# sensor_module.net
KiCad netlist of a schematic drawn in EAGLE
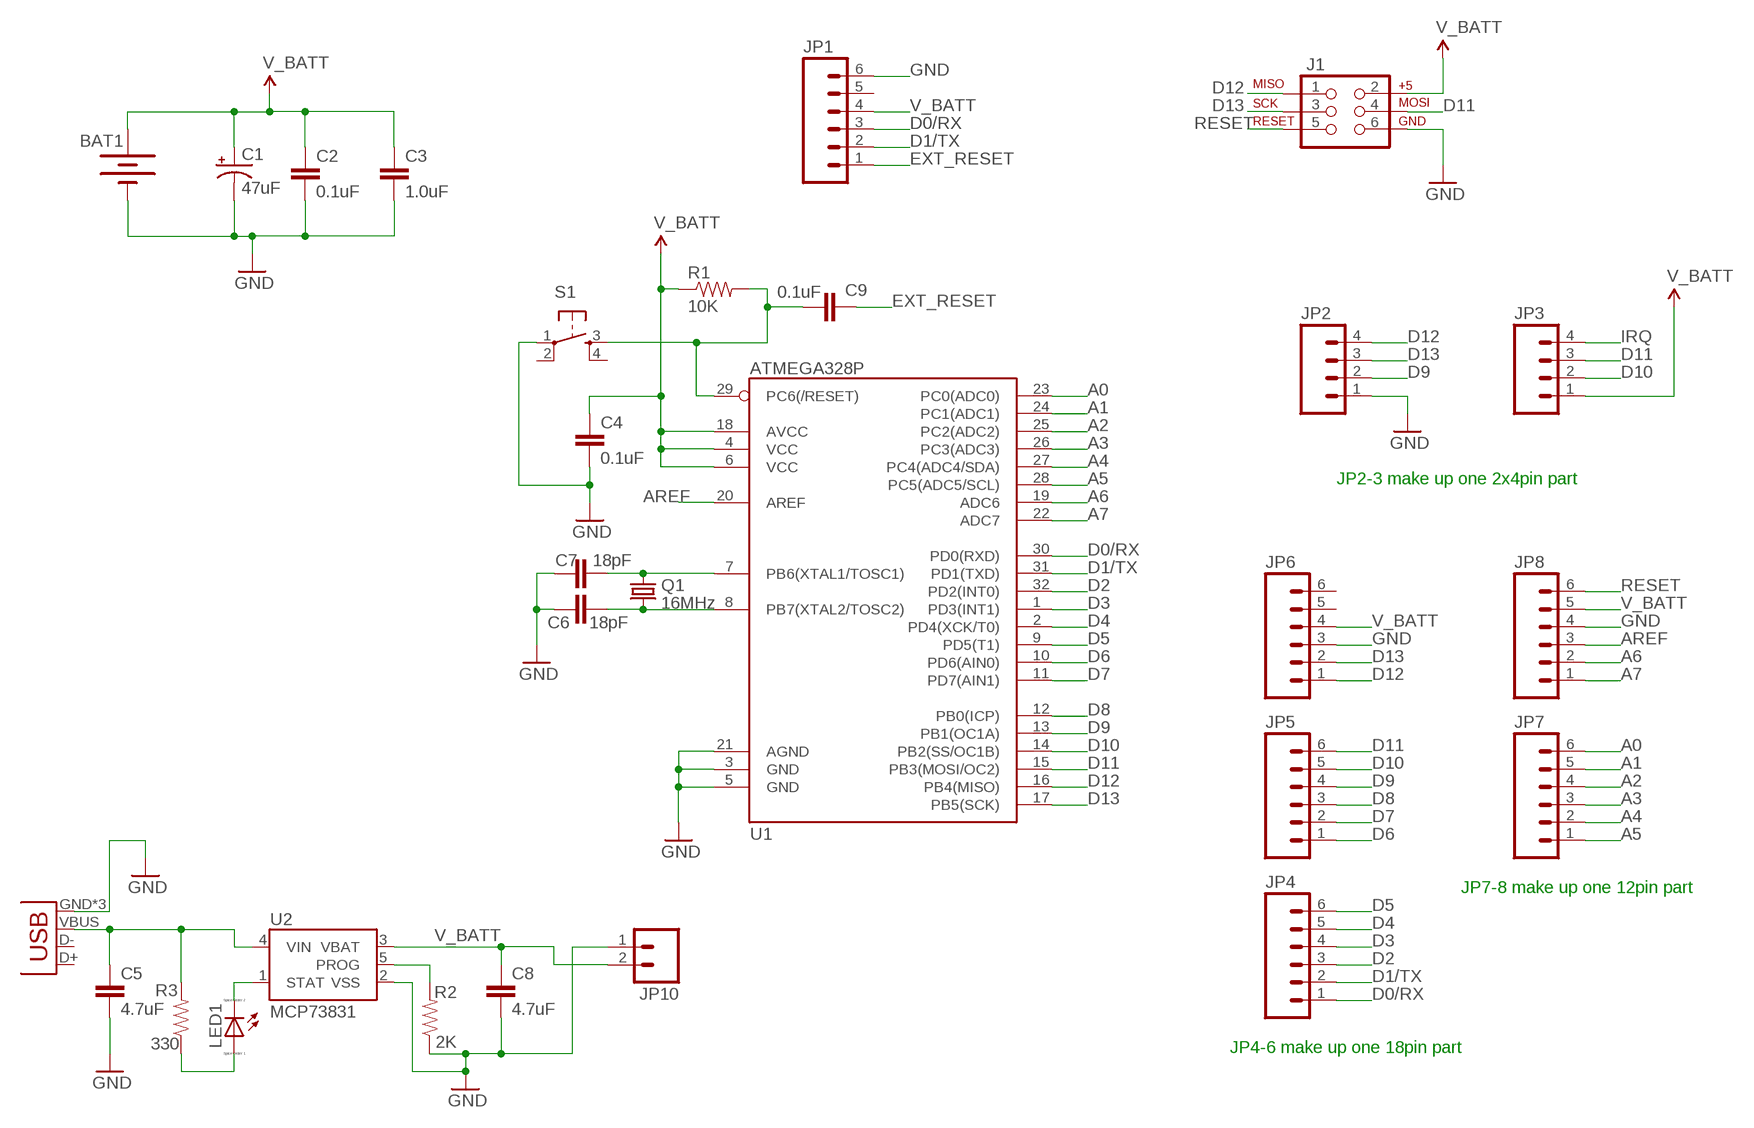
[diagram p0: schematic, sheet 1]

(export (version "E")
  (design (tool "Eeschema 10.0.6"))
  (components
    (comp (ref "BAT1")
      (value "20mm coincell")
      (footprint "eagle-import:BATTCON_20MM_4LEGS")
      (libsource (lib "eagle-import") (part "BATTERY20MM_4LEGS"))
    )
    (comp (ref "C1")
      (value "47uF")
      (footprint "eagle-import:EIA3216")
      (libsource (lib "eagle-import") (part "CAP_POL1206"))
    )
    (comp (ref "C2")
      (value "0.1uF")
      (footprint "eagle-import:0603-CAP")
      (libsource (lib "eagle-import") (part "0.1UF-25V-5%(0603)"))
    )
    (comp (ref "C3")
      (value "1.0uF")
      (footprint "eagle-import:0603-CAP")
      (libsource (lib "eagle-import") (part "1.0UF-16V-10%(0603)"))
    )
    (comp (ref "C4")
      (value "0.1uF")
      (footprint "eagle-import:0603-CAP")
      (libsource (lib "eagle-import") (part "0.1UF-25V-5%(0603)"))
    )
    (comp (ref "C5")
      (value "4.7uF")
      (footprint "eagle-import:0603-CAP")
      (libsource (lib "eagle-import") (part "CAP0603-CAP"))
    )
    (comp (ref "C6")
      (value "18pF")
      (footprint "eagle-import:0603-CAP")
      (libsource (lib "eagle-import") (part "22PF-50V-5%(0603)"))
    )
    (comp (ref "C7")
      (value "18pF")
      (footprint "eagle-import:0603-CAP")
      (libsource (lib "eagle-import") (part "22PF-50V-5%(0603)"))
    )
    (comp (ref "C8")
      (value "4.7uF")
      (footprint "eagle-import:0603-CAP")
      (libsource (lib "eagle-import") (part "CAP0603-CAP"))
    )
    (comp (ref "C9")
      (value "0.1uF")
      (footprint "eagle-import:0603-CAP")
      (libsource (lib "eagle-import") (part "0.1UF-25V-5%(0603)"))
    )
    (comp (ref "J1")
      (value "AVR_SPI_PRG_6PTH")
      (footprint "eagle-import:2X3")
      (libsource (lib "eagle-import") (part "AVR_SPI_PRG_6PTH"))
    )
    (comp (ref "JP1")
      (value "M06SIP")
      (footprint "eagle-import:1X06")
      (libsource (lib "eagle-import") (part "M06SIP"))
    )
    (comp (ref "JP2")
      (value "M04PTH")
      (footprint "eagle-import:1X04")
      (libsource (lib "eagle-import") (part "M04PTH"))
    )
    (comp (ref "JP3")
      (value "M04PTH")
      (footprint "eagle-import:1X04")
      (libsource (lib "eagle-import") (part "M04PTH"))
    )
    (comp (ref "JP4")
      (value "M06SIP")
      (footprint "eagle-import:1X06")
      (libsource (lib "eagle-import") (part "M06SIP"))
    )
    (comp (ref "JP5")
      (value "M06SIP")
      (footprint "eagle-import:1X06")
      (libsource (lib "eagle-import") (part "M06SIP"))
    )
    (comp (ref "JP6")
      (value "M06SIP")
      (footprint "eagle-import:1X06")
      (libsource (lib "eagle-import") (part "M06SIP"))
    )
    (comp (ref "JP7")
      (value "M06SIP")
      (footprint "eagle-import:1X06")
      (libsource (lib "eagle-import") (part "M06SIP"))
    )
    (comp (ref "JP8")
      (value "M06SIP")
      (footprint "eagle-import:1X06")
      (libsource (lib "eagle-import") (part "M06SIP"))
    )
    (comp (ref "JP9")
      (value "USB-MICROB")
      (footprint "eagle-import:USB-MICROB")
      (libsource (lib "eagle-import") (part "USB-MICROB"))
    )
    (comp (ref "JP10")
      (value "M02JST-PTH-2")
      (footprint "eagle-import:JST-2-PTH")
      (libsource (lib "eagle-import") (part "M02JST-PTH-2"))
    )
    (comp (ref "LED1")
      (value "LED_ESML0603")
      (footprint "eagle-import:LED_SML0603")
      (libsource (lib "eagle-import") (part "LED_ESML0603"))
    )
    (comp (ref "Q1")
      (value "16MHz")
      (footprint "eagle-import:HC49UP")
      (libsource (lib "eagle-import") (part "CRYSTALHC49UP"))
    )
    (comp (ref "R1")
      (value "10K")
      (footprint "eagle-import:0603-RES")
      (libsource (lib "eagle-import") (part "RESISTOR0603-RES"))
    )
    (comp (ref "R2")
      (value "2K")
      (footprint "eagle-import:0603-RES")
      (libsource (lib "eagle-import") (part "RESISTOR0603-RES"))
    )
    (comp (ref "R3")
      (value "330")
      (footprint "eagle-import:0603-RES")
      (libsource (lib "eagle-import") (part "RESISTOR0603-RES"))
    )
    (comp (ref "S1")
      (value "TAC_SWITCHSMD")
      (footprint "eagle-import:TACTILE_SWITCH_SMD")
      (libsource (lib "eagle-import") (part "TAC_SWITCHSMD"))
    )
    (comp (ref "U1")
      (value "ATMEGA328P")
      (footprint "eagle-import:TQFP32-08")
      (libsource (lib "eagle-import") (part "ATMEGA328_SMT"))
    )
    (comp (ref "U2")
      (value "MCP73831")
      (footprint "eagle-import:SOT23-5")
      (libsource (lib "eagle-import") (part "MCP73831"))
    )
  )
  (nets
    (net (code "1") (name "/A0") (class "Default")
      (node (ref "JP7") (pin "6") (pinfunction "6_6") (pintype "passive"))
      (node (ref "U1") (pin "23") (pinfunction "PC0(ADC0)_23") (pintype "bidirectional"))
    )
    (net (code "2") (name "/A1") (class "Default")
      (node (ref "JP7") (pin "5") (pinfunction "5_5") (pintype "passive"))
      (node (ref "U1") (pin "24") (pinfunction "PC1(ADC1)_24") (pintype "bidirectional"))
    )
    (net (code "3") (name "/A2") (class "Default")
      (node (ref "JP7") (pin "4") (pinfunction "4_4") (pintype "passive"))
      (node (ref "U1") (pin "25") (pinfunction "PC2(ADC2)_25") (pintype "bidirectional"))
    )
    (net (code "4") (name "/A3") (class "Default")
      (node (ref "JP7") (pin "3") (pinfunction "3_3") (pintype "passive"))
      (node (ref "U1") (pin "26") (pinfunction "PC3(ADC3)_26") (pintype "bidirectional"))
    )
    (net (code "5") (name "/A4") (class "Default")
      (node (ref "JP7") (pin "2") (pinfunction "2_2") (pintype "passive"))
      (node (ref "U1") (pin "27") (pinfunction "PC4(ADC4/SDA)_27") (pintype "bidirectional"))
    )
    (net (code "6") (name "/A5") (class "Default")
      (node (ref "JP7") (pin "1") (pinfunction "1_1") (pintype "passive"))
      (node (ref "U1") (pin "28") (pinfunction "PC5(ADC5/SCL)_28") (pintype "bidirectional"))
    )
    (net (code "7") (name "/A6") (class "Default")
      (node (ref "JP8") (pin "2") (pinfunction "2_2") (pintype "passive"))
      (node (ref "U1") (pin "19") (pinfunction "ADC6_19") (pintype "bidirectional"))
    )
    (net (code "8") (name "/A7") (class "Default")
      (node (ref "JP8") (pin "1") (pinfunction "1_1") (pintype "passive"))
      (node (ref "U1") (pin "22") (pinfunction "ADC7_22") (pintype "bidirectional"))
    )
    (net (code "9") (name "/AREF") (class "Default")
      (node (ref "JP8") (pin "3") (pinfunction "3_3") (pintype "passive"))
      (node (ref "U1") (pin "20") (pinfunction "AREF_20") (pintype "bidirectional"))
    )
    (net (code "10") (name "/D0{slash}RX") (class "Default")
      (node (ref "JP1") (pin "3") (pinfunction "3_3") (pintype "passive"))
      (node (ref "JP4") (pin "1") (pinfunction "1_1") (pintype "passive"))
      (node (ref "U1") (pin "30") (pinfunction "PD0(RXD)_30") (pintype "bidirectional"))
    )
    (net (code "11") (name "/D1{slash}TX") (class "Default")
      (node (ref "JP1") (pin "2") (pinfunction "2_2") (pintype "passive"))
      (node (ref "JP4") (pin "2") (pinfunction "2_2") (pintype "passive"))
      (node (ref "U1") (pin "31") (pinfunction "PD1(TXD)_31") (pintype "bidirectional"))
    )
    (net (code "12") (name "/D2") (class "Default")
      (node (ref "JP4") (pin "3") (pinfunction "3_3") (pintype "passive"))
      (node (ref "U1") (pin "32") (pinfunction "PD2(INT0)_32") (pintype "bidirectional"))
    )
    (net (code "13") (name "/D3") (class "Default")
      (node (ref "JP4") (pin "4") (pinfunction "4_4") (pintype "passive"))
      (node (ref "U1") (pin "1") (pinfunction "PD3(INT1)_1") (pintype "bidirectional"))
    )
    (net (code "14") (name "/D4") (class "Default")
      (node (ref "JP4") (pin "5") (pinfunction "5_5") (pintype "passive"))
      (node (ref "U1") (pin "2") (pinfunction "PD4(XCK/T0)_2") (pintype "bidirectional"))
    )
    (net (code "15") (name "/D5") (class "Default")
      (node (ref "JP4") (pin "6") (pinfunction "6_6") (pintype "passive"))
      (node (ref "U1") (pin "9") (pinfunction "PD5(T1)_9") (pintype "bidirectional"))
    )
    (net (code "16") (name "/D6") (class "Default")
      (node (ref "JP5") (pin "1") (pinfunction "1_1") (pintype "passive"))
      (node (ref "U1") (pin "10") (pinfunction "PD6(AIN0)_10") (pintype "bidirectional"))
    )
    (net (code "17") (name "/D7") (class "Default")
      (node (ref "JP5") (pin "2") (pinfunction "2_2") (pintype "passive"))
      (node (ref "U1") (pin "11") (pinfunction "PD7(AIN1)_11") (pintype "bidirectional"))
    )
    (net (code "18") (name "/D8") (class "Default")
      (node (ref "JP5") (pin "3") (pinfunction "3_3") (pintype "passive"))
      (node (ref "U1") (pin "12") (pinfunction "PB0(ICP)_12") (pintype "bidirectional"))
    )
    (net (code "19") (name "/D9") (class "Default")
      (node (ref "JP2") (pin "2") (pinfunction "2_2") (pintype "passive"))
      (node (ref "JP5") (pin "4") (pinfunction "4_4") (pintype "passive"))
      (node (ref "U1") (pin "13") (pinfunction "PB1(OC1A)_13") (pintype "bidirectional"))
    )
    (net (code "20") (name "/D10") (class "Default")
      (node (ref "JP3") (pin "2") (pinfunction "2_2") (pintype "passive"))
      (node (ref "JP5") (pin "5") (pinfunction "5_5") (pintype "passive"))
      (node (ref "U1") (pin "14") (pinfunction "PB2(SS/OC1B)_14") (pintype "bidirectional"))
    )
    (net (code "21") (name "/D11") (class "Default")
      (node (ref "J1") (pin "4") (pinfunction "4_4") (pintype "passive"))
      (node (ref "JP3") (pin "3") (pinfunction "3_3") (pintype "passive"))
      (node (ref "JP5") (pin "6") (pinfunction "6_6") (pintype "passive"))
      (node (ref "U1") (pin "15") (pinfunction "PB3(MOSI/OC2)_15") (pintype "bidirectional"))
    )
    (net (code "22") (name "/D12") (class "Default")
      (node (ref "J1") (pin "1") (pinfunction "1_1") (pintype "passive"))
      (node (ref "JP2") (pin "4") (pinfunction "4_4") (pintype "passive"))
      (node (ref "JP6") (pin "1") (pinfunction "1_1") (pintype "passive"))
      (node (ref "U1") (pin "16") (pinfunction "PB4(MISO)_16") (pintype "bidirectional"))
    )
    (net (code "23") (name "/D13") (class "Default")
      (node (ref "J1") (pin "3") (pinfunction "3_3") (pintype "passive"))
      (node (ref "JP2") (pin "3") (pinfunction "3_3") (pintype "passive"))
      (node (ref "JP6") (pin "2") (pinfunction "2_2") (pintype "passive"))
      (node (ref "U1") (pin "17") (pinfunction "PB5(SCK)_17") (pintype "bidirectional"))
    )
    (net (code "24") (name "/EXT_RESET") (class "Default")
      (node (ref "C9") (pin "1") (pinfunction "1_1") (pintype "passive"))
      (node (ref "JP1") (pin "1") (pinfunction "1_1") (pintype "passive"))
    )
    (net (code "25") (name "/IRQ") (class "Default")
      (node (ref "JP3") (pin "4") (pinfunction "4_4") (pintype "passive"))
    )
    (net (code "26") (name "/RESET") (class "Default")
      (node (ref "C9") (pin "2") (pinfunction "2_2") (pintype "passive"))
      (node (ref "J1") (pin "5") (pinfunction "5_5") (pintype "passive"))
      (node (ref "JP8") (pin "6") (pinfunction "6_6") (pintype "passive"))
      (node (ref "R1") (pin "2") (pinfunction "2_2") (pintype "passive"))
      (node (ref "S1") (pin "3") (pinfunction "3_3") (pintype "passive"))
      (node (ref "U1") (pin "29") (pinfunction "PC6(/RESET)_29") (pintype "bidirectional"))
    )
    (net (code "27") (name "GND") (class "Default")
      (node (ref "BAT1") (pin "2") (pinfunction "-_2") (pintype "power_in"))
      (node (ref "C1") (pin "C") (pinfunction "-_C") (pintype "passive"))
      (node (ref "C2") (pin "2") (pinfunction "2_2") (pintype "passive"))
      (node (ref "C3") (pin "2") (pinfunction "2_2") (pintype "passive"))
      (node (ref "C4") (pin "2") (pinfunction "2_2") (pintype "passive"))
      (node (ref "C5") (pin "2") (pinfunction "2_2") (pintype "passive"))
      (node (ref "C6") (pin "1") (pinfunction "1_1") (pintype "passive"))
      (node (ref "C7") (pin "2") (pinfunction "2_2") (pintype "passive"))
      (node (ref "C8") (pin "2") (pinfunction "2_2") (pintype "passive"))
      (node (ref "J1") (pin "6") (pinfunction "6_6") (pintype "passive"))
      (node (ref "JP1") (pin "6") (pinfunction "6_6") (pintype "passive"))
      (node (ref "JP10") (pin "1") (pinfunction "1_1") (pintype "passive"))
      (node (ref "JP2") (pin "1") (pinfunction "1_1") (pintype "passive"))
      (node (ref "JP6") (pin "3") (pinfunction "3_3") (pintype "passive"))
      (node (ref "JP8") (pin "4") (pinfunction "4_4") (pintype "passive"))
      (node (ref "JP9") (pin "GND") (pinfunction "GND_GND") (pintype "bidirectional"))
      (node (ref "JP9") (pin "MT1") (pinfunction "GND_MT1") (pintype "bidirectional"))
      (node (ref "JP9") (pin "MT2") (pinfunction "GND_MT2") (pintype "bidirectional"))
      (node (ref "R2") (pin "1") (pinfunction "1_1") (pintype "passive"))
      (node (ref "S1") (pin "1") (pinfunction "1_1") (pintype "passive"))
      (node (ref "U1") (pin "21") (pinfunction "AGND_21") (pintype "bidirectional"))
      (node (ref "U1") (pin "3") (pinfunction "GND_3") (pintype "bidirectional"))
      (node (ref "U1") (pin "5") (pinfunction "GND_5") (pintype "bidirectional"))
      (node (ref "U2") (pin "2") (pinfunction "VSS_2") (pintype "power_in"))
    )
    (net (code "28") (name "Net-(LED1-PadA)") (class "Default")
      (node (ref "LED1") (pin "A") (pinfunction "A_A") (pintype "passive"))
      (node (ref "R3") (pin "1") (pinfunction "1_1") (pintype "passive"))
    )
    (net (code "29") (name "Net-(U1-PB6(XTAL1{slash}TOSC1))") (class "Default")
      (node (ref "C7") (pin "1") (pinfunction "1_1") (pintype "passive"))
      (node (ref "Q1") (pin "1") (pinfunction "1_1") (pintype "passive"))
      (node (ref "U1") (pin "7") (pinfunction "PB6(XTAL1/TOSC1)_7") (pintype "bidirectional"))
    )
    (net (code "30") (name "Net-(U1-PB7(XTAL2{slash}TOSC2))") (class "Default")
      (node (ref "C6") (pin "2") (pinfunction "2_2") (pintype "passive"))
      (node (ref "Q1") (pin "2") (pinfunction "2_2") (pintype "passive"))
      (node (ref "U1") (pin "8") (pinfunction "PB7(XTAL2/TOSC2)_8") (pintype "bidirectional"))
    )
    (net (code "31") (name "Net-(U2-PROG)") (class "Default")
      (node (ref "R2") (pin "2") (pinfunction "2_2") (pintype "passive"))
      (node (ref "U2") (pin "5") (pinfunction "PROG_5") (pintype "input"))
    )
    (net (code "32") (name "Net-(U2-STAT)") (class "Default")
      (node (ref "LED1") (pin "C") (pinfunction "C_C") (pintype "passive"))
      (node (ref "U2") (pin "1") (pinfunction "STAT_1") (pintype "output"))
    )
    (net (code "33") (name "Net-(U2-VIN)") (class "Default")
      (node (ref "C5") (pin "1") (pinfunction "1_1") (pintype "passive"))
      (node (ref "JP9") (pin "VBUS") (pinfunction "VBUS_VBUS") (pintype "bidirectional"))
      (node (ref "R3") (pin "2") (pinfunction "2_2") (pintype "passive"))
      (node (ref "U2") (pin "4") (pinfunction "VIN_4") (pintype "power_in"))
    )
    (net (code "34") (name "V_BATT") (class "Default")
      (node (ref "BAT1") (pin "1") (pinfunction "+_1") (pintype "power_in"))
      (node (ref "C1") (pin "A") (pinfunction "+_A") (pintype "passive"))
      (node (ref "C2") (pin "1") (pinfunction "1_1") (pintype "passive"))
      (node (ref "C3") (pin "1") (pinfunction "1_1") (pintype "passive"))
      (node (ref "C4") (pin "1") (pinfunction "1_1") (pintype "passive"))
      (node (ref "C8") (pin "1") (pinfunction "1_1") (pintype "passive"))
      (node (ref "J1") (pin "2") (pinfunction "2_2") (pintype "passive"))
      (node (ref "JP1") (pin "4") (pinfunction "4_4") (pintype "passive"))
      (node (ref "JP10") (pin "2") (pinfunction "2_2") (pintype "passive"))
      (node (ref "JP3") (pin "1") (pinfunction "1_1") (pintype "passive"))
      (node (ref "JP6") (pin "4") (pinfunction "4_4") (pintype "passive"))
      (node (ref "JP8") (pin "5") (pinfunction "5_5") (pintype "passive"))
      (node (ref "R1") (pin "1") (pinfunction "1_1") (pintype "passive"))
      (node (ref "U1") (pin "18") (pinfunction "AVCC_18") (pintype "bidirectional"))
      (node (ref "U1") (pin "4") (pinfunction "VCC_4") (pintype "bidirectional"))
      (node (ref "U1") (pin "6") (pinfunction "VCC_6") (pintype "bidirectional"))
      (node (ref "U2") (pin "3") (pinfunction "VBAT_3") (pintype "power_in"))
    )
    (net (code "35") (name "unconnected-(JP1-Pad5)") (class "Default")
      (node (ref "JP1") (pin "5") (pinfunction "5_5") (pintype "passive"))
    )
    (net (code "36") (name "unconnected-(JP6-Pad5)") (class "Default")
      (node (ref "JP6") (pin "5") (pinfunction "5_5") (pintype "passive"))
    )
    (net (code "37") (name "unconnected-(JP6-Pad6)") (class "Default")
      (node (ref "JP6") (pin "6") (pinfunction "6_6") (pintype "passive"))
    )
    (net (code "38") (name "unconnected-(JP9-PadD+)") (class "Default")
      (node (ref "JP9") (pin "D+") (pinfunction "D+_D+") (pintype "bidirectional"))
    )
    (net (code "39") (name "unconnected-(JP9-PadD-)") (class "Default")
      (node (ref "JP9") (pin "D-") (pinfunction "D-_D-") (pintype "bidirectional"))
    )
    (net (code "40") (name "unconnected-(S1-Pad2)") (class "Default")
      (node (ref "S1") (pin "2") (pinfunction "2_2") (pintype "passive"))
    )
    (net (code "41") (name "unconnected-(S1-Pad4)") (class "Default")
      (node (ref "S1") (pin "4") (pinfunction "4_4") (pintype "passive"))
    )
  )
)
